# EspressoWemos.net
KiCad netlist of a schematic drawn in EAGLE
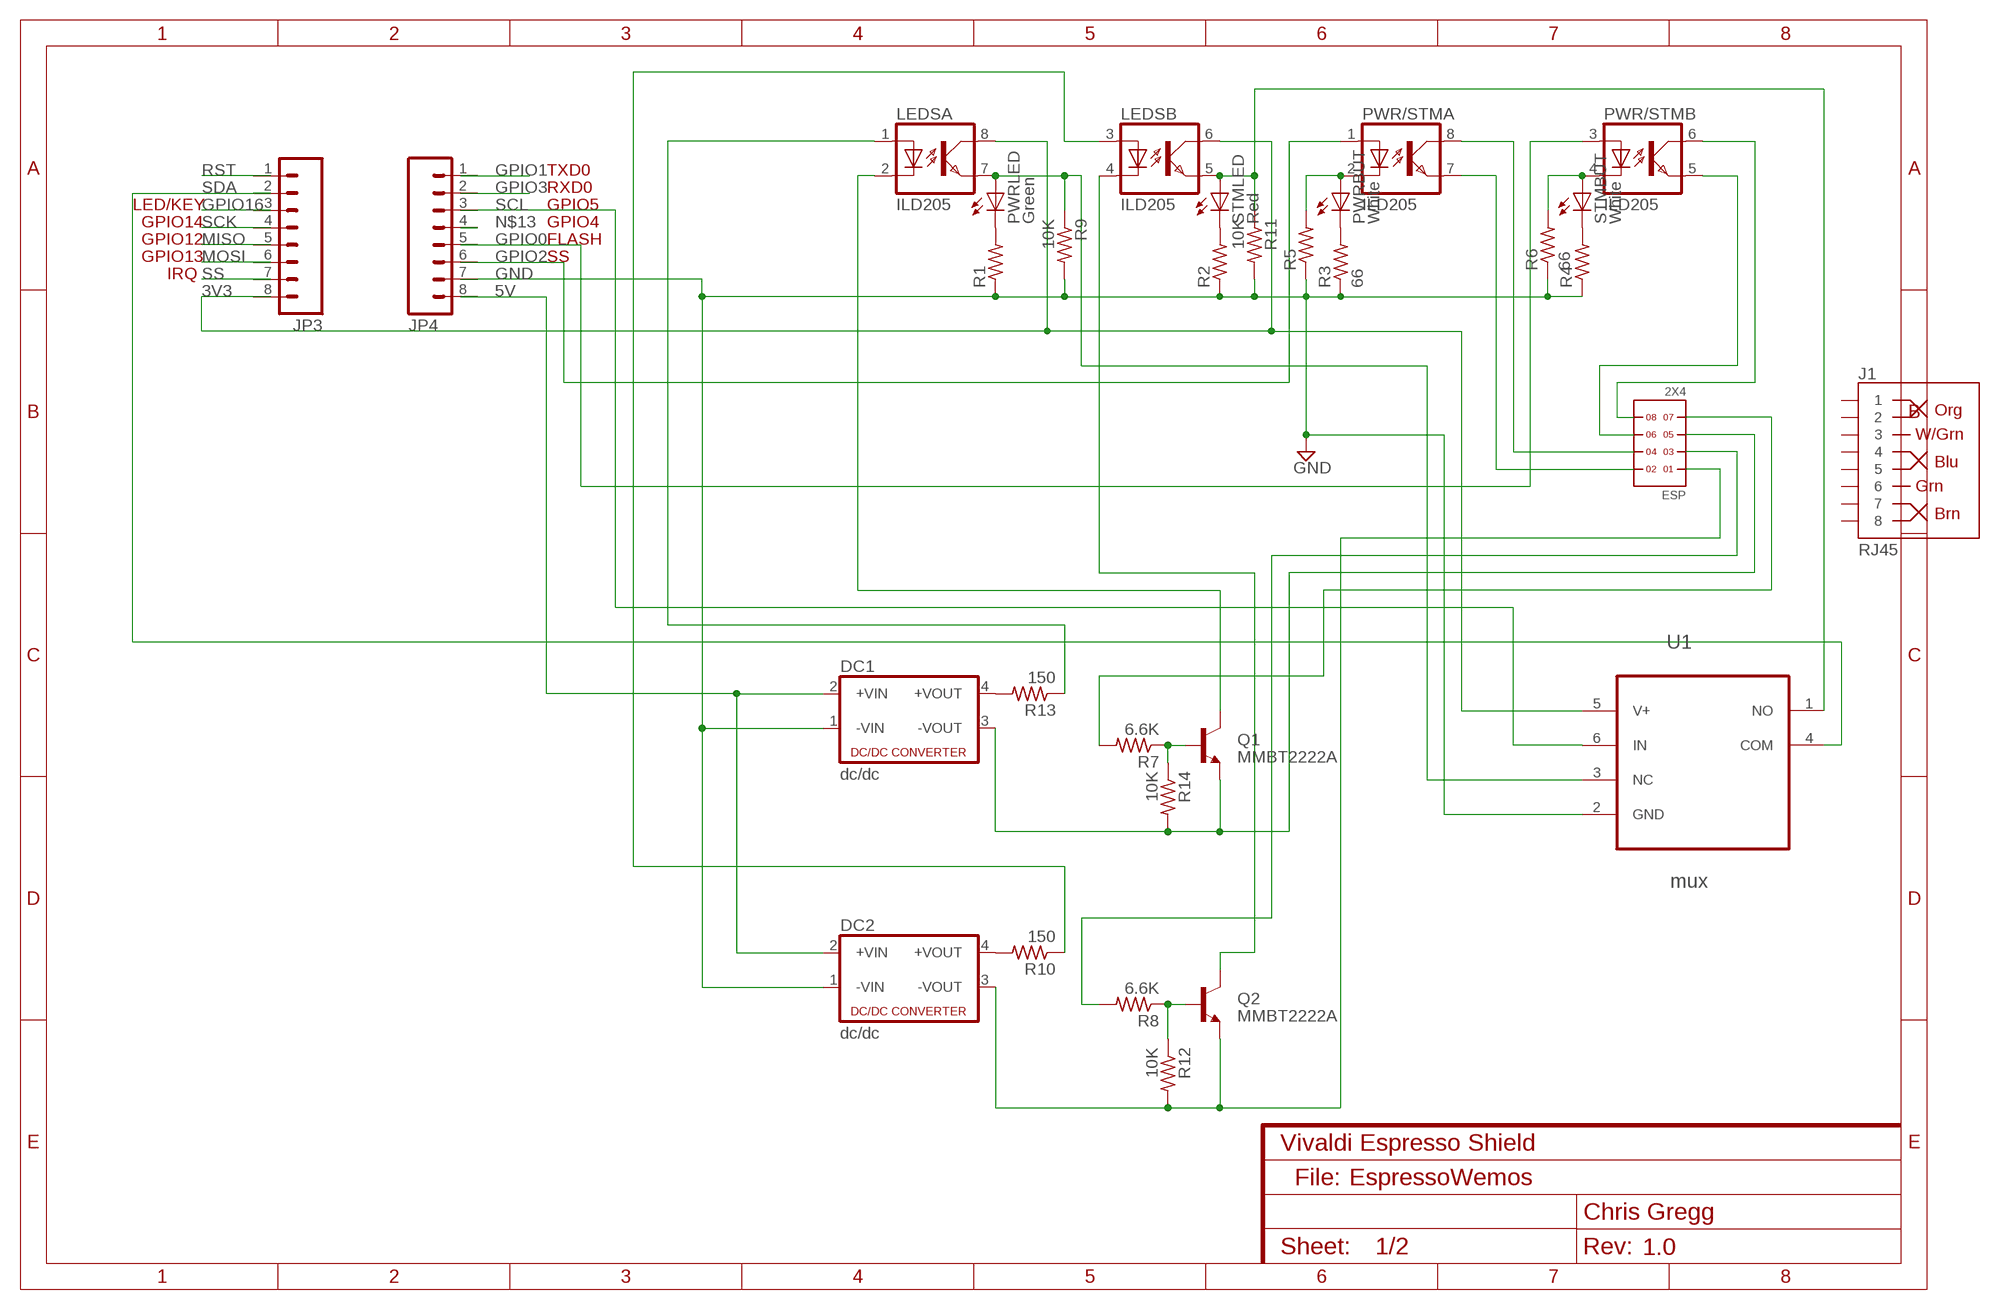
[diagram p0: schematic, sheet 1]

(export (version "E")
  (design (tool "Eeschema 10.0.6"))
  (components
    (comp (ref "DC1")
      (value "dc/dc")
      (footprint "eagle-import:4SIL")
      (libsource (lib "eagle-import") (part "VA-?S0505"))
    )
    (comp (ref "DC2")
      (value "dc/dc")
      (footprint "eagle-import:4SIL")
      (libsource (lib "eagle-import") (part "VA-?S0505"))
    )
    (comp (ref "ESP")
      (value "2X4")
      (footprint "eagle-import:2X4")
      (libsource (lib "eagle-import") (part "2X4"))
    )
    (comp (ref "J1")
      (value "RJ45")
      (footprint "eagle-import:RJ45-8")
      (libsource (lib "eagle-import") (part "RJ45-8PTH"))
    )
    (comp (ref "JP3")
      (value "M08NO_SILK_FEMALE_PTH")
      (footprint "eagle-import:1X08_NO_SILK")
      (libsource (lib "eagle-import") (part "M08NO_SILK_FEMALE_PTH"))
    )
    (comp (ref "JP4")
      (value "M08NO_SILK_FEMALE_PTH")
      (footprint "eagle-import:1X08_NO_SILK")
      (libsource (lib "eagle-import") (part "M08NO_SILK_FEMALE_PTH"))
    )
    (comp (ref "LEDS")
      (value "ILD205")
      (footprint "eagle-import:SOIC08")
      (fields (field (name "MF") "VISHAY/TELEFUNKEN") (field (name "MPN") "ILD205T"))
      (libsource (lib "eagle-import") (part "ILD205"))
    )
    (comp (ref "PWR/STM")
      (value "ILD205")
      (footprint "eagle-import:SOIC08")
      (fields (field (name "MF") "VISHAY/TELEFUNKEN") (field (name "MPN") "ILD205T"))
      (libsource (lib "eagle-import") (part "ILD205"))
    )
    (comp (ref "PWRBUT")
      (value "White")
      (footprint "eagle-import:SML1206")
      (libsource (lib "eagle-import") (part "LEDSML1206"))
    )
    (comp (ref "PWRLED")
      (value "Green")
      (footprint "eagle-import:SML1206")
      (libsource (lib "eagle-import") (part "LEDSML1206"))
    )
    (comp (ref "Q1")
      (value "MMBT2222A")
      (footprint "eagle-import:SOT23-3")
      (libsource (lib "eagle-import") (part "TRANSISTOR_NPNMMBT2222A"))
    )
    (comp (ref "Q2")
      (value "MMBT2222A")
      (footprint "eagle-import:SOT23-3")
      (libsource (lib "eagle-import") (part "TRANSISTOR_NPNMMBT2222A"))
    )
    (comp (ref "R1")
      (value "R-US_R1206")
      (footprint "eagle-import:R1206")
      (libsource (lib "eagle-import") (part "R-US_R1206"))
    )
    (comp (ref "R2")
      (value "R-US_R1206")
      (footprint "eagle-import:R1206")
      (libsource (lib "eagle-import") (part "R-US_R1206"))
    )
    (comp (ref "R3")
      (value "66")
      (footprint "eagle-import:R1206")
      (libsource (lib "eagle-import") (part "R-US_R1206"))
    )
    (comp (ref "R4")
      (value "R-US_R1206")
      (footprint "eagle-import:R1206")
      (libsource (lib "eagle-import") (part "R-US_R1206"))
    )
    (comp (ref "R5")
      (value "R-US_R1206")
      (footprint "eagle-import:R1206")
      (libsource (lib "eagle-import") (part "R-US_R1206"))
    )
    (comp (ref "R6")
      (value "66")
      (footprint "eagle-import:R1206")
      (libsource (lib "eagle-import") (part "R-US_R1206"))
    )
    (comp (ref "R7")
      (value "6.6K")
      (footprint "eagle-import:R1206")
      (libsource (lib "eagle-import") (part "R-US_R1206"))
    )
    (comp (ref "R8")
      (value "6.6K")
      (footprint "eagle-import:R1206")
      (libsource (lib "eagle-import") (part "R-US_R1206"))
    )
    (comp (ref "R9")
      (value "10K")
      (footprint "eagle-import:R1206")
      (libsource (lib "eagle-import") (part "R-US_R1206"))
    )
    (comp (ref "R10")
      (value "150")
      (footprint "eagle-import:R1206")
      (libsource (lib "eagle-import") (part "R-US_R1206"))
    )
    (comp (ref "R11")
      (value "10K")
      (footprint "eagle-import:R1206")
      (libsource (lib "eagle-import") (part "R-US_R1206"))
    )
    (comp (ref "R12")
      (value "10K")
      (footprint "eagle-import:R1206")
      (libsource (lib "eagle-import") (part "R-US_R1206"))
    )
    (comp (ref "R13")
      (value "150")
      (footprint "eagle-import:R1206")
      (libsource (lib "eagle-import") (part "R-US_R1206"))
    )
    (comp (ref "R14")
      (value "10K")
      (footprint "eagle-import:R1206")
      (libsource (lib "eagle-import") (part "R-US_R1206"))
    )
    (comp (ref "STMBUT")
      (value "White")
      (footprint "eagle-import:SML1206")
      (libsource (lib "eagle-import") (part "LEDSML1206"))
    )
    (comp (ref "STMLED")
      (value "Red")
      (footprint "eagle-import:SML1206")
      (libsource (lib "eagle-import") (part "LEDSML1206"))
    )
    (comp (ref "U1")
      (value "mux")
      (footprint "eagle-import:SOT95P280X145-6N")
      (fields (field (name "MPN") "TS5A3159DBVR"))
      (libsource (lib "eagle-import") (part "TS5A3159DBVR"))
    )
  )
  (nets
    (net (code "1") (name "3V3") (class "Default")
      (node (ref "JP3") (pin "8") (pinfunction "8_8") (pintype "passive"))
      (node (ref "LEDS") (pin "6") (pinfunction "COL_6") (pintype "passive"))
      (node (ref "LEDS") (pin "8") (pinfunction "COL_8") (pintype "passive"))
      (node (ref "U1") (pin "5") (pinfunction "V+_5") (pintype "power_in"))
    )
    (net (code "2") (name "5V") (class "Default")
      (node (ref "DC1") (pin "2") (pinfunction "+VIN_2") (pintype "passive"))
      (node (ref "DC2") (pin "2") (pinfunction "+VIN_2") (pintype "passive"))
      (node (ref "JP4") (pin "8") (pinfunction "8_8") (pintype "passive"))
    )
    (net (code "3") (name "GND") (class "Default")
      (node (ref "DC1") (pin "1") (pinfunction "-VIN_1") (pintype "passive"))
      (node (ref "DC2") (pin "1") (pinfunction "-VIN_1") (pintype "passive"))
      (node (ref "JP4") (pin "7") (pinfunction "7_7") (pintype "passive"))
      (node (ref "R1") (pin "1") (pinfunction "1_1") (pintype "passive"))
      (node (ref "R11") (pin "2") (pinfunction "2_2") (pintype "passive"))
      (node (ref "R2") (pin "1") (pinfunction "1_1") (pintype "passive"))
      (node (ref "R3") (pin "1") (pinfunction "1_1") (pintype "passive"))
      (node (ref "R4") (pin "1") (pinfunction "1_1") (pintype "passive"))
      (node (ref "R5") (pin "1") (pinfunction "1_1") (pintype "passive"))
      (node (ref "R6") (pin "1") (pinfunction "1_1") (pintype "passive"))
      (node (ref "R9") (pin "2") (pinfunction "2_2") (pintype "passive"))
      (node (ref "U1") (pin "2") (pinfunction "GND_2") (pintype "passive"))
    )
    (net (code "4") (name "GPIO0") (class "Default")
      (node (ref "JP4") (pin "5") (pinfunction "5_5") (pintype "passive"))
      (node (ref "PWR/STM") (pin "3") (pinfunction "A_3") (pintype "passive"))
    )
    (net (code "5") (name "GPIO1") (class "Default")
      (node (ref "JP4") (pin "1") (pinfunction "1_1") (pintype "passive"))
    )
    (net (code "6") (name "GPIO2") (class "Default")
      (node (ref "JP4") (pin "6") (pinfunction "6_6") (pintype "passive"))
      (node (ref "PWR/STM") (pin "1") (pinfunction "A_1") (pintype "passive"))
    )
    (net (code "7") (name "GPIO3") (class "Default")
      (node (ref "JP4") (pin "2") (pinfunction "2_2") (pintype "passive"))
    )
    (net (code "8") (name "GPIO16") (class "Default")
      (node (ref "JP3") (pin "3") (pinfunction "3_3") (pintype "passive"))
    )
    (net (code "9") (name "MISO") (class "Default")
      (node (ref "JP3") (pin "5") (pinfunction "5_5") (pintype "passive"))
    )
    (net (code "10") (name "MOSI") (class "Default")
      (node (ref "JP3") (pin "6") (pinfunction "6_6") (pintype "passive"))
    )
    (net (code "11") (name "N$13") (class "Default")
      (node (ref "JP4") (pin "4") (pinfunction "4_4") (pintype "passive"))
    )
    (net (code "12") (name "Net-(DC1-+VOUT)") (class "Default")
      (node (ref "DC1") (pin "4") (pinfunction "+VOUT_4") (pintype "passive"))
      (node (ref "R13") (pin "2") (pinfunction "2_2") (pintype "passive"))
    )
    (net (code "13") (name "Net-(DC1--VOUT)") (class "Default")
      (node (ref "DC1") (pin "3") (pinfunction "-VOUT_3") (pintype "passive"))
      (node (ref "ESP") (pin "5") (pinfunction "5_5") (pintype "bidirectional"))
      (node (ref "Q1") (pin "2") (pinfunction "E_2") (pintype "passive"))
      (node (ref "R14") (pin "2") (pinfunction "2_2") (pintype "passive"))
    )
    (net (code "14") (name "Net-(DC2-+VOUT)") (class "Default")
      (node (ref "DC2") (pin "4") (pinfunction "+VOUT_4") (pintype "passive"))
      (node (ref "R10") (pin "2") (pinfunction "2_2") (pintype "passive"))
    )
    (net (code "15") (name "Net-(DC2--VOUT)") (class "Default")
      (node (ref "DC2") (pin "3") (pinfunction "-VOUT_3") (pintype "passive"))
      (node (ref "ESP") (pin "1") (pinfunction "1_1") (pintype "bidirectional"))
      (node (ref "Q2") (pin "2") (pinfunction "E_2") (pintype "passive"))
      (node (ref "R12") (pin "2") (pinfunction "2_2") (pintype "passive"))
    )
    (net (code "16") (name "Net-(ESP-Pad3)") (class "Default")
      (node (ref "ESP") (pin "3") (pinfunction "3_3") (pintype "bidirectional"))
      (node (ref "R8") (pin "2") (pinfunction "2_2") (pintype "passive"))
    )
    (net (code "17") (name "Net-(ESP-Pad7)") (class "Default")
      (node (ref "ESP") (pin "7") (pinfunction "7_7") (pintype "bidirectional"))
      (node (ref "R7") (pin "2") (pinfunction "2_2") (pintype "passive"))
    )
    (net (code "18") (name "Net-(LEDSA-A)") (class "Default")
      (node (ref "LEDS") (pin "1") (pinfunction "A_1") (pintype "passive"))
      (node (ref "R13") (pin "1") (pinfunction "1_1") (pintype "passive"))
    )
    (net (code "19") (name "Net-(LEDSA-C)") (class "Default")
      (node (ref "LEDS") (pin "2") (pinfunction "C_2") (pintype "passive"))
      (node (ref "Q1") (pin "3") (pinfunction "C_3") (pintype "passive"))
    )
    (net (code "20") (name "Net-(LEDSA-EMIT)") (class "Default")
      (node (ref "LEDS") (pin "7") (pinfunction "EMIT_7") (pintype "passive"))
      (node (ref "PWRLED") (pin "A") (pinfunction "A_A") (pintype "passive"))
      (node (ref "R9") (pin "1") (pinfunction "1_1") (pintype "passive"))
      (node (ref "U1") (pin "3") (pinfunction "NC_3") (pintype "passive"))
    )
    (net (code "21") (name "Net-(LEDSB-A)") (class "Default")
      (node (ref "LEDS") (pin "3") (pinfunction "A_3") (pintype "passive"))
      (node (ref "R10") (pin "1") (pinfunction "1_1") (pintype "passive"))
    )
    (net (code "22") (name "Net-(LEDSB-C)") (class "Default")
      (node (ref "LEDS") (pin "4") (pinfunction "C_4") (pintype "passive"))
      (node (ref "Q2") (pin "3") (pinfunction "C_3") (pintype "passive"))
    )
    (net (code "23") (name "Net-(LEDSB-EMIT)") (class "Default")
      (node (ref "LEDS") (pin "5") (pinfunction "EMIT_5") (pintype "passive"))
      (node (ref "R11") (pin "1") (pinfunction "1_1") (pintype "passive"))
      (node (ref "STMLED") (pin "A") (pinfunction "A_A") (pintype "passive"))
      (node (ref "U1") (pin "1") (pinfunction "NO_1") (pintype "passive"))
    )
    (net (code "24") (name "Net-(PWR/STMA-C)") (class "Default")
      (node (ref "PWR/STM") (pin "2") (pinfunction "C_2") (pintype "passive"))
      (node (ref "PWRBUT") (pin "A") (pinfunction "A_A") (pintype "passive"))
      (node (ref "R5") (pin "2") (pinfunction "2_2") (pintype "passive"))
    )
    (net (code "25") (name "Net-(PWR/STMA-COL)") (class "Default")
      (node (ref "ESP") (pin "4") (pinfunction "4_4") (pintype "bidirectional"))
      (node (ref "PWR/STM") (pin "8") (pinfunction "COL_8") (pintype "passive"))
    )
    (net (code "26") (name "Net-(PWR/STMA-EMIT)") (class "Default")
      (node (ref "ESP") (pin "2") (pinfunction "2_2") (pintype "bidirectional"))
      (node (ref "PWR/STM") (pin "7") (pinfunction "EMIT_7") (pintype "passive"))
    )
    (net (code "27") (name "Net-(PWR/STMB-C)") (class "Default")
      (node (ref "PWR/STM") (pin "4") (pinfunction "C_4") (pintype "passive"))
      (node (ref "R6") (pin "2") (pinfunction "2_2") (pintype "passive"))
      (node (ref "STMBUT") (pin "A") (pinfunction "A_A") (pintype "passive"))
    )
    (net (code "28") (name "Net-(PWR/STMB-COL)") (class "Default")
      (node (ref "ESP") (pin "8") (pinfunction "8_8") (pintype "bidirectional"))
      (node (ref "PWR/STM") (pin "6") (pinfunction "COL_6") (pintype "passive"))
    )
    (net (code "29") (name "Net-(PWR/STMB-EMIT)") (class "Default")
      (node (ref "ESP") (pin "6") (pinfunction "6_6") (pintype "bidirectional"))
      (node (ref "PWR/STM") (pin "5") (pinfunction "EMIT_5") (pintype "passive"))
    )
    (net (code "30") (name "Net-(PWRBUT-PadC)") (class "Default")
      (node (ref "PWRBUT") (pin "C") (pinfunction "C_C") (pintype "passive"))
      (node (ref "R3") (pin "2") (pinfunction "2_2") (pintype "passive"))
    )
    (net (code "31") (name "Net-(PWRLED-PadC)") (class "Default")
      (node (ref "PWRLED") (pin "C") (pinfunction "C_C") (pintype "passive"))
      (node (ref "R1") (pin "2") (pinfunction "2_2") (pintype "passive"))
    )
    (net (code "32") (name "Net-(Q1-B)") (class "Default")
      (node (ref "Q1") (pin "1") (pinfunction "B_1") (pintype "passive"))
      (node (ref "R14") (pin "1") (pinfunction "1_1") (pintype "passive"))
      (node (ref "R7") (pin "1") (pinfunction "1_1") (pintype "passive"))
    )
    (net (code "33") (name "Net-(Q2-B)") (class "Default")
      (node (ref "Q2") (pin "1") (pinfunction "B_1") (pintype "passive"))
      (node (ref "R12") (pin "1") (pinfunction "1_1") (pintype "passive"))
      (node (ref "R8") (pin "1") (pinfunction "1_1") (pintype "passive"))
    )
    (net (code "34") (name "Net-(R2-Pad2)") (class "Default")
      (node (ref "R2") (pin "2") (pinfunction "2_2") (pintype "passive"))
      (node (ref "STMLED") (pin "C") (pinfunction "C_C") (pintype "passive"))
    )
    (net (code "35") (name "Net-(R4-Pad2)") (class "Default")
      (node (ref "R4") (pin "2") (pinfunction "2_2") (pintype "passive"))
      (node (ref "STMBUT") (pin "C") (pinfunction "C_C") (pintype "passive"))
    )
    (net (code "36") (name "RST") (class "Default")
      (node (ref "JP3") (pin "1") (pinfunction "1_1") (pintype "passive"))
    )
    (net (code "37") (name "SCK") (class "Default")
      (node (ref "JP3") (pin "4") (pinfunction "4_4") (pintype "passive"))
    )
    (net (code "38") (name "SCL") (class "Default")
      (node (ref "JP4") (pin "3") (pinfunction "3_3") (pintype "passive"))
      (node (ref "U1") (pin "6") (pinfunction "IN_6") (pintype "input"))
    )
    (net (code "39") (name "SDA") (class "Default")
      (node (ref "JP3") (pin "2") (pinfunction "2_2") (pintype "passive"))
      (node (ref "U1") (pin "4") (pinfunction "COM_4") (pintype "passive"))
    )
    (net (code "40") (name "SS") (class "Default")
      (node (ref "JP3") (pin "7") (pinfunction "7_7") (pintype "passive"))
    )
    (net (code "41") (name "unconnected-(J1-Pad1)") (class "Default")
      (node (ref "J1") (pin "1") (pinfunction "1_1") (pintype "bidirectional"))
    )
    (net (code "42") (name "unconnected-(J1-Pad2)") (class "Default")
      (node (ref "J1") (pin "2") (pinfunction "2_2") (pintype "bidirectional"))
    )
    (net (code "43") (name "unconnected-(J1-Pad3)") (class "Default")
      (node (ref "J1") (pin "3") (pinfunction "3_3") (pintype "bidirectional"))
    )
    (net (code "44") (name "unconnected-(J1-Pad4)") (class "Default")
      (node (ref "J1") (pin "4") (pinfunction "4_4") (pintype "bidirectional"))
    )
    (net (code "45") (name "unconnected-(J1-Pad5)") (class "Default")
      (node (ref "J1") (pin "5") (pinfunction "5_5") (pintype "bidirectional"))
    )
    (net (code "46") (name "unconnected-(J1-Pad6)") (class "Default")
      (node (ref "J1") (pin "6") (pinfunction "6_6") (pintype "bidirectional"))
    )
    (net (code "47") (name "unconnected-(J1-Pad7)") (class "Default")
      (node (ref "J1") (pin "7") (pinfunction "7_7") (pintype "bidirectional"))
    )
    (net (code "48") (name "unconnected-(J1-Pad8)") (class "Default")
      (node (ref "J1") (pin "8") (pinfunction "8_8") (pintype "bidirectional"))
    )
  )
)
